# NodeMCU_Weather_v_1_0.net
KiCad netlist of a schematic drawn in EAGLE
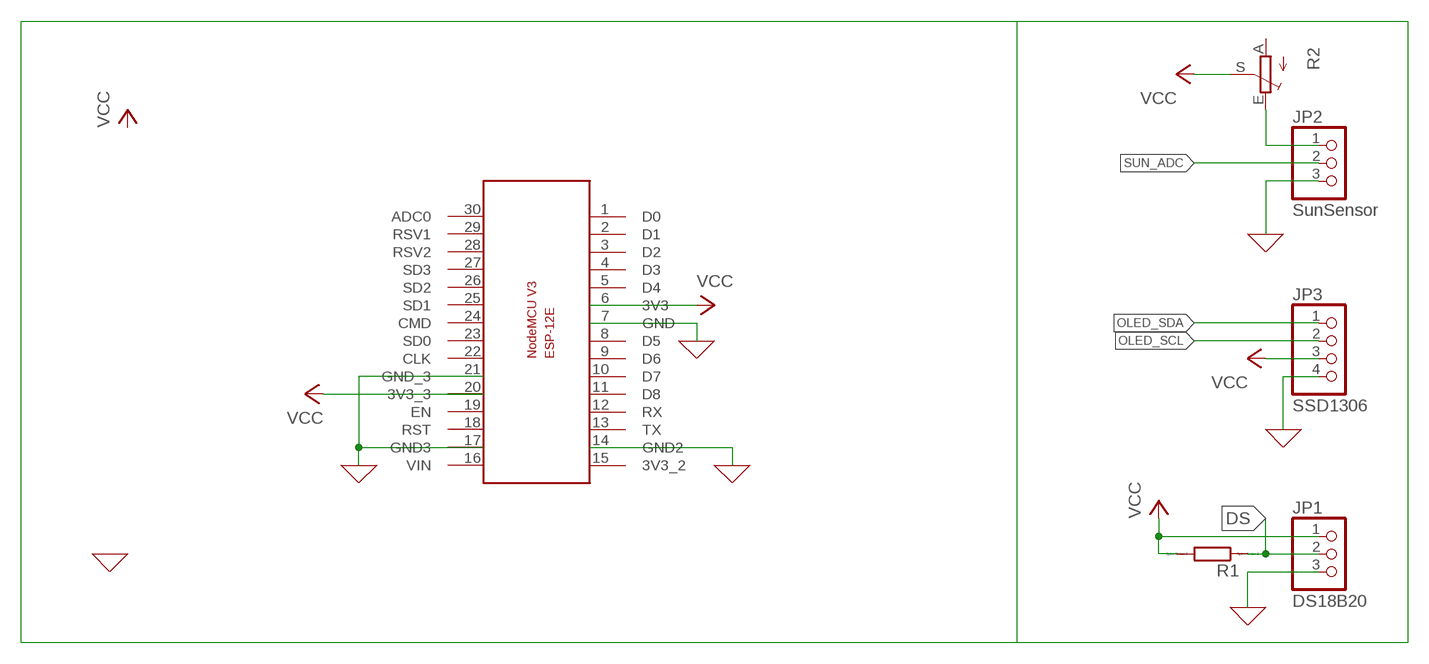
[diagram p0: schematic, sheet 1]

(export (version "E")
  (design (tool "Eeschema 10.0.6"))
  (components
    (comp (ref "JP1")
      (value "DS18B20")
      (footprint "eagle-import:1X03")
      (libsource (lib "eagle-import") (part "PINHD-1X3"))
    )
    (comp (ref "JP2")
      (value "SunSensor")
      (footprint "eagle-import:1X03")
      (libsource (lib "eagle-import") (part "PINHD-1X3"))
    )
    (comp (ref "JP3")
      (value "SSD1306")
      (footprint "eagle-import:1X04")
      (libsource (lib "eagle-import") (part "PINHD-1X4"))
    )
    (comp (ref "R1")
      (value "R0204/7")
      (footprint "eagle-import:0204_7")
      (libsource (lib "eagle-import") (part "R0204/7"))
    )
    (comp (ref "R2")
      (value "TRIM_EU-B25P")
      (footprint "eagle-import:B25P")
      (libsource (lib "eagle-import") (part "TRIM_EU-B25P"))
    )
    (comp (ref "U$1")
      (value "NODEMCUESP8266")
      (footprint "eagle-import:NODEMCUESP8266")
      (libsource (lib "eagle-import") (part "NODEMCUESP8266"))
    )
  )
  (nets
    (net (code "1") (name "DS") (class "Default")
      (node (ref "JP1") (pin "2") (pinfunction "2_2") (pintype "passive"))
      (node (ref "R1") (pin "1") (pinfunction "1_1") (pintype "passive"))
    )
    (net (code "2") (name "GND") (class "Default")
      (node (ref "JP1") (pin "3") (pinfunction "3_3") (pintype "passive"))
      (node (ref "JP2") (pin "3") (pinfunction "3_3") (pintype "passive"))
      (node (ref "JP3") (pin "4") (pinfunction "4_4") (pintype "passive"))
      (node (ref "U$1") (pin "14") (pinfunction "GND2_14") (pintype "bidirectional"))
      (node (ref "U$1") (pin "17") (pinfunction "GND3_17") (pintype "bidirectional"))
      (node (ref "U$1") (pin "21") (pinfunction "GND_3_21") (pintype "bidirectional"))
      (node (ref "U$1") (pin "7") (pinfunction "GND_7") (pintype "bidirectional"))
    )
    (net (code "3") (name "Net-(JP2-Pad1)") (class "Default")
      (node (ref "JP2") (pin "1") (pinfunction "1_1") (pintype "passive"))
      (node (ref "R2") (pin "E") (pinfunction "E_E") (pintype "passive"))
    )
    (net (code "4") (name "OLED_SCL") (class "Default")
      (node (ref "JP3") (pin "2") (pinfunction "2_2") (pintype "passive"))
    )
    (net (code "5") (name "OLED_SDA") (class "Default")
      (node (ref "JP3") (pin "1") (pinfunction "1_1") (pintype "passive"))
    )
    (net (code "6") (name "SUN_ADC") (class "Default")
      (node (ref "JP2") (pin "2") (pinfunction "2_2") (pintype "passive"))
    )
    (net (code "7") (name "VCC") (class "Default")
      (node (ref "JP1") (pin "1") (pinfunction "1_1") (pintype "passive"))
      (node (ref "JP3") (pin "3") (pinfunction "3_3") (pintype "passive"))
      (node (ref "R1") (pin "2") (pinfunction "2_2") (pintype "passive"))
      (node (ref "R2") (pin "S") (pinfunction "S_S") (pintype "passive"))
      (node (ref "U$1") (pin "20") (pinfunction "3V3_3_20") (pintype "bidirectional"))
      (node (ref "U$1") (pin "6") (pinfunction "3V3_6") (pintype "bidirectional"))
    )
    (net (code "8") (name "unconnected-(R2-PadA)") (class "Default")
      (node (ref "R2") (pin "A") (pinfunction "A_A") (pintype "passive"))
    )
    (net (code "9") (name "unconnected-(U$1-3V3_2-Pad15)") (class "Default")
      (node (ref "U$1") (pin "15") (pinfunction "3V3_2_15") (pintype "bidirectional"))
    )
    (net (code "10") (name "unconnected-(U$1-ADC0-Pad30)") (class "Default")
      (node (ref "U$1") (pin "30") (pinfunction "ADC0_30") (pintype "bidirectional"))
    )
    (net (code "11") (name "unconnected-(U$1-CLK-Pad22)") (class "Default")
      (node (ref "U$1") (pin "22") (pinfunction "CLK_22") (pintype "bidirectional"))
    )
    (net (code "12") (name "unconnected-(U$1-CMD-Pad24)") (class "Default")
      (node (ref "U$1") (pin "24") (pinfunction "CMD_24") (pintype "bidirectional"))
    )
    (net (code "13") (name "unconnected-(U$1-D0-Pad1)") (class "Default")
      (node (ref "U$1") (pin "1") (pinfunction "D0_1") (pintype "bidirectional"))
    )
    (net (code "14") (name "unconnected-(U$1-D1-Pad2)") (class "Default")
      (node (ref "U$1") (pin "2") (pinfunction "D1_2") (pintype "bidirectional"))
    )
    (net (code "15") (name "unconnected-(U$1-D2-Pad3)") (class "Default")
      (node (ref "U$1") (pin "3") (pinfunction "D2_3") (pintype "bidirectional"))
    )
    (net (code "16") (name "unconnected-(U$1-D3-Pad4)") (class "Default")
      (node (ref "U$1") (pin "4") (pinfunction "D3_4") (pintype "bidirectional"))
    )
    (net (code "17") (name "unconnected-(U$1-D4-Pad5)") (class "Default")
      (node (ref "U$1") (pin "5") (pinfunction "D4_5") (pintype "bidirectional"))
    )
    (net (code "18") (name "unconnected-(U$1-D5-Pad8)") (class "Default")
      (node (ref "U$1") (pin "8") (pinfunction "D5_8") (pintype "bidirectional"))
    )
    (net (code "19") (name "unconnected-(U$1-D6-Pad9)") (class "Default")
      (node (ref "U$1") (pin "9") (pinfunction "D6_9") (pintype "bidirectional"))
    )
    (net (code "20") (name "unconnected-(U$1-D7-Pad10)") (class "Default")
      (node (ref "U$1") (pin "10") (pinfunction "D7_10") (pintype "bidirectional"))
    )
    (net (code "21") (name "unconnected-(U$1-D8-Pad11)") (class "Default")
      (node (ref "U$1") (pin "11") (pinfunction "D8_11") (pintype "bidirectional"))
    )
    (net (code "22") (name "unconnected-(U$1-EN-Pad19)") (class "Default")
      (node (ref "U$1") (pin "19") (pinfunction "EN_19") (pintype "bidirectional"))
    )
    (net (code "23") (name "unconnected-(U$1-RST-Pad18)") (class "Default")
      (node (ref "U$1") (pin "18") (pinfunction "RST_18") (pintype "bidirectional"))
    )
    (net (code "24") (name "unconnected-(U$1-RSV1-Pad29)") (class "Default")
      (node (ref "U$1") (pin "29") (pinfunction "RSV1_29") (pintype "bidirectional"))
    )
    (net (code "25") (name "unconnected-(U$1-RSV2-Pad28)") (class "Default")
      (node (ref "U$1") (pin "28") (pinfunction "RSV2_28") (pintype "bidirectional"))
    )
    (net (code "26") (name "unconnected-(U$1-RX-Pad12)") (class "Default")
      (node (ref "U$1") (pin "12") (pinfunction "RX_12") (pintype "bidirectional"))
    )
    (net (code "27") (name "unconnected-(U$1-SD0-Pad23)") (class "Default")
      (node (ref "U$1") (pin "23") (pinfunction "SD0_23") (pintype "bidirectional"))
    )
    (net (code "28") (name "unconnected-(U$1-SD1-Pad25)") (class "Default")
      (node (ref "U$1") (pin "25") (pinfunction "SD1_25") (pintype "bidirectional"))
    )
    (net (code "29") (name "unconnected-(U$1-SD2-Pad26)") (class "Default")
      (node (ref "U$1") (pin "26") (pinfunction "SD2_26") (pintype "bidirectional"))
    )
    (net (code "30") (name "unconnected-(U$1-SD3-Pad27)") (class "Default")
      (node (ref "U$1") (pin "27") (pinfunction "SD3_27") (pintype "bidirectional"))
    )
    (net (code "31") (name "unconnected-(U$1-TX-Pad13)") (class "Default")
      (node (ref "U$1") (pin "13") (pinfunction "TX_13") (pintype "bidirectional"))
    )
    (net (code "32") (name "unconnected-(U$1-VIN-Pad16)") (class "Default")
      (node (ref "U$1") (pin "16") (pinfunction "VIN_16") (pintype "bidirectional"))
    )
  )
)
